# LED_Display.net
KiCad netlist of a schematic drawn in Altium Designer
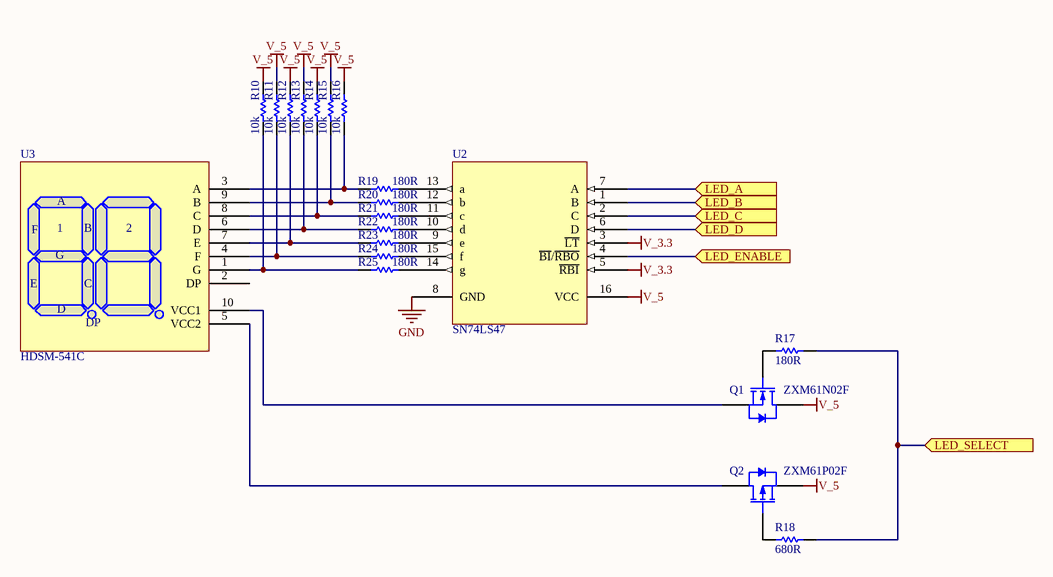
[diagram p0: LED_Display.SchDoc]

(export (version "E")
  (design (tool "Eeschema 10.0.6"))
  (components
    (comp (ref "Q1")
      (value "ZXM61N02F")
      (footprint "SOT-23")
      (description "20V N-channel enhancement mode MOSFET")
      (fields (field (name "MANUFACTURER") "Zetex") (field (name "PART NUMBER") "TF_ZXM61N02F"))
      (libsource (lib "ENEL429_3") (part "TF_ZXM61N02F"))
    )
    (comp (ref "Q2")
      (value "ZXM61P02F")
      (footprint "SOT23")
      (description "20V P-channel enhancement mode MOSFET")
      (fields (field (name "MANUFACTURER") "Zetex") (field (name "PART NUMBER") "TF_ZXM61P02F"))
      (libsource (lib "ENEL429_3") (part "TF_ZXM61P02F"))
    )
    (comp (ref "R10")
      (value "10k")
      (footprint "0603")
      (description "RES 10.0K OHM 1/10W 1% 0603 SMD")
      (fields (field (name "MANUFACTURER") "Yageo") (field (name "PART NUMBER") "RS_10k 0603"))
      (libsource (lib "ENEL429_3") (part "RS_10k 0603"))
    )
    (comp (ref "R11")
      (value "10k")
      (footprint "0603")
      (description "RES 10.0K OHM 1/10W 1% 0603 SMD")
      (fields (field (name "MANUFACTURER") "Yageo") (field (name "PART NUMBER") "RS_10k 0603"))
      (libsource (lib "ENEL429_3") (part "RS_10k 0603"))
    )
    (comp (ref "R12")
      (value "10k")
      (footprint "0603")
      (description "RES 10.0K OHM 1/10W 1% 0603 SMD")
      (fields (field (name "MANUFACTURER") "Yageo") (field (name "PART NUMBER") "RS_10k 0603"))
      (libsource (lib "ENEL429_3") (part "RS_10k 0603"))
    )
    (comp (ref "R13")
      (value "10k")
      (footprint "0603")
      (description "RES 10.0K OHM 1/10W 1% 0603 SMD")
      (fields (field (name "MANUFACTURER") "Yageo") (field (name "PART NUMBER") "RS_10k 0603"))
      (libsource (lib "ENEL429_3") (part "RS_10k 0603"))
    )
    (comp (ref "R14")
      (value "10k")
      (footprint "0603")
      (description "RES 10.0K OHM 1/10W 1% 0603 SMD")
      (fields (field (name "MANUFACTURER") "Yageo") (field (name "PART NUMBER") "RS_10k 0603"))
      (libsource (lib "ENEL429_3") (part "RS_10k 0603"))
    )
    (comp (ref "R15")
      (value "10k")
      (footprint "0603")
      (description "RES 10.0K OHM 1/10W 1% 0603 SMD")
      (fields (field (name "MANUFACTURER") "Yageo") (field (name "PART NUMBER") "RS_10k 0603"))
      (libsource (lib "ENEL429_3") (part "RS_10k 0603"))
    )
    (comp (ref "R16")
      (value "10k")
      (footprint "0603")
      (description "RES 10.0K OHM 1/10W 1% 0603 SMD")
      (fields (field (name "MANUFACTURER") "Yageo") (field (name "PART NUMBER") "RS_10k 0603"))
      (libsource (lib "ENEL429_3") (part "RS_10k 0603"))
    )
    (comp (ref "R17")
      (value "180R")
      (footprint "0603")
      (description "RES 180OHM 1/10W 1% 0603 SMD")
      (fields (field (name "MANUFACTURER") "Panasonic - ECG") (field (name "PART NUMBER") "RS_180R 0603"))
      (libsource (lib "ENEL429_3") (part "RS_180R 0603"))
    )
    (comp (ref "R18")
      (value "680R")
      (footprint "0603")
      (description "RES 680 OHM 1/10W 1% 0603 SMD")
      (fields (field (name "MANUFACTURER") "Yageo") (field (name "PART NUMBER") "RS_680R 0603"))
      (libsource (lib "ENEL429_3") (part "RS_680R 0603"))
    )
    (comp (ref "R19")
      (value "180R")
      (footprint "0603")
      (description "RES 180OHM 1/10W 1% 0603 SMD")
      (fields (field (name "MANUFACTURER") "Panasonic - ECG") (field (name "PART NUMBER") "RS_180R 0603"))
      (libsource (lib "ENEL429_3") (part "RS_180R 0603"))
    )
    (comp (ref "R20")
      (value "180R")
      (footprint "0603")
      (description "RES 180OHM 1/10W 1% 0603 SMD")
      (fields (field (name "MANUFACTURER") "Panasonic - ECG") (field (name "PART NUMBER") "RS_180R 0603"))
      (libsource (lib "ENEL429_3") (part "RS_180R 0603"))
    )
    (comp (ref "R21")
      (value "180R")
      (footprint "0603")
      (description "RES 180OHM 1/10W 1% 0603 SMD")
      (fields (field (name "MANUFACTURER") "Panasonic - ECG") (field (name "PART NUMBER") "RS_180R 0603"))
      (libsource (lib "ENEL429_3") (part "RS_180R 0603"))
    )
    (comp (ref "R22")
      (value "180R")
      (footprint "0603")
      (description "RES 180OHM 1/10W 1% 0603 SMD")
      (fields (field (name "MANUFACTURER") "Panasonic - ECG") (field (name "PART NUMBER") "RS_180R 0603"))
      (libsource (lib "ENEL429_3") (part "RS_180R 0603"))
    )
    (comp (ref "R23")
      (value "180R")
      (footprint "0603")
      (description "RES 180OHM 1/10W 1% 0603 SMD")
      (fields (field (name "MANUFACTURER") "Panasonic - ECG") (field (name "PART NUMBER") "RS_180R 0603"))
      (libsource (lib "ENEL429_3") (part "RS_180R 0603"))
    )
    (comp (ref "R24")
      (value "180R")
      (footprint "0603")
      (description "RES 180OHM 1/10W 1% 0603 SMD")
      (fields (field (name "MANUFACTURER") "Panasonic - ECG") (field (name "PART NUMBER") "RS_180R 0603"))
      (libsource (lib "ENEL429_3") (part "RS_180R 0603"))
    )
    (comp (ref "R25")
      (value "180R")
      (footprint "0603")
      (description "RES 180OHM 1/10W 1% 0603 SMD")
      (fields (field (name "MANUFACTURER") "Panasonic - ECG") (field (name "PART NUMBER") "RS_180R 0603"))
      (libsource (lib "ENEL429_3") (part "RS_180R 0603"))
    )
    (comp (ref "U2")
      (value "SN74LS47")
      (footprint "SOP127P780X200-16N")
      (fields (field (name "MANUFACTURER") "Texas Instruments"))
      (libsource (lib "Wacky_1") (part "SN74LS47"))
    )
    (comp (ref "U3")
      (value "HDSM-541C")
      (footprint "HDSM-541C")
      (description "2 character 7 segment display")
      (fields (field (name "MANUFACTURER") "AVAGO TECHNOLOGIES"))
      (libsource (lib "Wacky_1") (part "HDSM-541C"))
    )
  )
  (nets
    (net (code "1") (name "/LED_A") (class "Default")
      (node (ref "U2") (pin "7") (pinfunction "A_7") (pintype "input"))
    )
    (net (code "2") (name "/LED_B") (class "Default")
      (node (ref "U2") (pin "1") (pinfunction "B_1") (pintype "input"))
    )
    (net (code "3") (name "/LED_C") (class "Default")
      (node (ref "U2") (pin "2") (pinfunction "C_2") (pintype "input"))
    )
    (net (code "4") (name "/LED_D") (class "Default")
      (node (ref "U2") (pin "6") (pinfunction "D_6") (pintype "input"))
    )
    (net (code "5") (name "/LED_ENABLE") (class "Default")
      (node (ref "U2") (pin "4") (pinfunction "~{BI}/~{RBO}_4") (pintype "input"))
    )
    (net (code "6") (name "/LED_SELECT") (class "Default")
      (node (ref "R17") (pin "2") (pinfunction "2_2") (pintype "passive"))
      (node (ref "R18") (pin "2") (pinfunction "2_2") (pintype "passive"))
    )
    (net (code "7") (name "GND") (class "Default")
      (node (ref "U2") (pin "8") (pinfunction "GND_8") (pintype "passive"))
    )
    (net (code "8") (name "Net-(Q1-G)") (class "Default")
      (node (ref "Q1") (pin "1") (pinfunction "G_1") (pintype "passive"))
      (node (ref "R17") (pin "1") (pinfunction "1_1") (pintype "passive"))
    )
    (net (code "9") (name "Net-(Q1-S)") (class "Default")
      (node (ref "Q1") (pin "2") (pinfunction "S_2") (pintype "passive"))
      (node (ref "U3") (pin "10") (pinfunction "VCC1_10") (pintype "passive"))
    )
    (net (code "10") (name "Net-(Q2-D)") (class "Default")
      (node (ref "Q2") (pin "3") (pinfunction "D_3") (pintype "passive"))
      (node (ref "U3") (pin "5") (pinfunction "VCC2_5") (pintype "passive"))
    )
    (net (code "11") (name "Net-(Q2-G)") (class "Default")
      (node (ref "Q2") (pin "1") (pinfunction "G_1") (pintype "passive"))
      (node (ref "R18") (pin "1") (pinfunction "1_1") (pintype "passive"))
    )
    (net (code "12") (name "Net-(U2-a)") (class "Default")
      (node (ref "R19") (pin "2") (pinfunction "2_2") (pintype "passive"))
      (node (ref "U2") (pin "13") (pinfunction "a_13") (pintype "output"))
    )
    (net (code "13") (name "Net-(U2-b)") (class "Default")
      (node (ref "R20") (pin "2") (pinfunction "2_2") (pintype "passive"))
      (node (ref "U2") (pin "12") (pinfunction "b_12") (pintype "output"))
    )
    (net (code "14") (name "Net-(U2-c)") (class "Default")
      (node (ref "R21") (pin "2") (pinfunction "2_2") (pintype "passive"))
      (node (ref "U2") (pin "11") (pinfunction "c_11") (pintype "output"))
    )
    (net (code "15") (name "Net-(U2-d)") (class "Default")
      (node (ref "R22") (pin "2") (pinfunction "2_2") (pintype "passive"))
      (node (ref "U2") (pin "10") (pinfunction "d_10") (pintype "output"))
    )
    (net (code "16") (name "Net-(U2-e)") (class "Default")
      (node (ref "R23") (pin "2") (pinfunction "2_2") (pintype "passive"))
      (node (ref "U2") (pin "9") (pinfunction "e_9") (pintype "output"))
    )
    (net (code "17") (name "Net-(U2-f)") (class "Default")
      (node (ref "R24") (pin "2") (pinfunction "2_2") (pintype "passive"))
      (node (ref "U2") (pin "15") (pinfunction "f_15") (pintype "output"))
    )
    (net (code "18") (name "Net-(U2-g)") (class "Default")
      (node (ref "R25") (pin "2") (pinfunction "2_2") (pintype "passive"))
      (node (ref "U2") (pin "14") (pinfunction "g_14") (pintype "output"))
    )
    (net (code "19") (name "Net-(U3-A)") (class "Default")
      (node (ref "R16") (pin "1") (pinfunction "1_1") (pintype "passive"))
      (node (ref "R19") (pin "1") (pinfunction "1_1") (pintype "passive"))
      (node (ref "U3") (pin "3") (pinfunction "A_3") (pintype "passive"))
    )
    (net (code "20") (name "Net-(U3-B)") (class "Default")
      (node (ref "R15") (pin "1") (pinfunction "1_1") (pintype "passive"))
      (node (ref "R20") (pin "1") (pinfunction "1_1") (pintype "passive"))
      (node (ref "U3") (pin "9") (pinfunction "B_9") (pintype "passive"))
    )
    (net (code "21") (name "Net-(U3-C)") (class "Default")
      (node (ref "R14") (pin "1") (pinfunction "1_1") (pintype "passive"))
      (node (ref "R21") (pin "1") (pinfunction "1_1") (pintype "passive"))
      (node (ref "U3") (pin "8") (pinfunction "C_8") (pintype "passive"))
    )
    (net (code "22") (name "Net-(U3-D)") (class "Default")
      (node (ref "R13") (pin "1") (pinfunction "1_1") (pintype "passive"))
      (node (ref "R22") (pin "1") (pinfunction "1_1") (pintype "passive"))
      (node (ref "U3") (pin "6") (pinfunction "D_6") (pintype "passive"))
    )
    (net (code "23") (name "Net-(U3-E)") (class "Default")
      (node (ref "R12") (pin "1") (pinfunction "1_1") (pintype "passive"))
      (node (ref "R23") (pin "1") (pinfunction "1_1") (pintype "passive"))
      (node (ref "U3") (pin "7") (pinfunction "E_7") (pintype "passive"))
    )
    (net (code "24") (name "Net-(U3-F)") (class "Default")
      (node (ref "R11") (pin "1") (pinfunction "1_1") (pintype "passive"))
      (node (ref "R24") (pin "1") (pinfunction "1_1") (pintype "passive"))
      (node (ref "U3") (pin "4") (pinfunction "F_4") (pintype "passive"))
    )
    (net (code "25") (name "Net-(U3-G)") (class "Default")
      (node (ref "R10") (pin "1") (pinfunction "1_1") (pintype "passive"))
      (node (ref "R25") (pin "1") (pinfunction "1_1") (pintype "passive"))
      (node (ref "U3") (pin "1") (pinfunction "G_1") (pintype "passive"))
    )
    (net (code "26") (name "V_3.3") (class "Default")
      (node (ref "U2") (pin "3") (pinfunction "~{LT}_3") (pintype "input"))
      (node (ref "U2") (pin "5") (pinfunction "~{RBI}_5") (pintype "input"))
    )
    (net (code "27") (name "V_5") (class "Default")
      (node (ref "Q1") (pin "3") (pinfunction "D_3") (pintype "passive"))
      (node (ref "Q2") (pin "2") (pinfunction "S_2") (pintype "passive"))
      (node (ref "R10") (pin "2") (pinfunction "2_2") (pintype "passive"))
      (node (ref "R11") (pin "2") (pinfunction "2_2") (pintype "passive"))
      (node (ref "R12") (pin "2") (pinfunction "2_2") (pintype "passive"))
      (node (ref "R13") (pin "2") (pinfunction "2_2") (pintype "passive"))
      (node (ref "R14") (pin "2") (pinfunction "2_2") (pintype "passive"))
      (node (ref "R15") (pin "2") (pinfunction "2_2") (pintype "passive"))
      (node (ref "R16") (pin "2") (pinfunction "2_2") (pintype "passive"))
      (node (ref "U2") (pin "16") (pinfunction "VCC_16") (pintype "power_in"))
    )
    (net (code "28") (name "unconnected-(U3-DP-Pad2)") (class "Default")
      (node (ref "U3") (pin "2") (pinfunction "DP_2") (pintype "passive"))
    )
  )
)
